# MAXIM-ADC2.net
KiCad netlist of a schematic drawn in Altium Designer
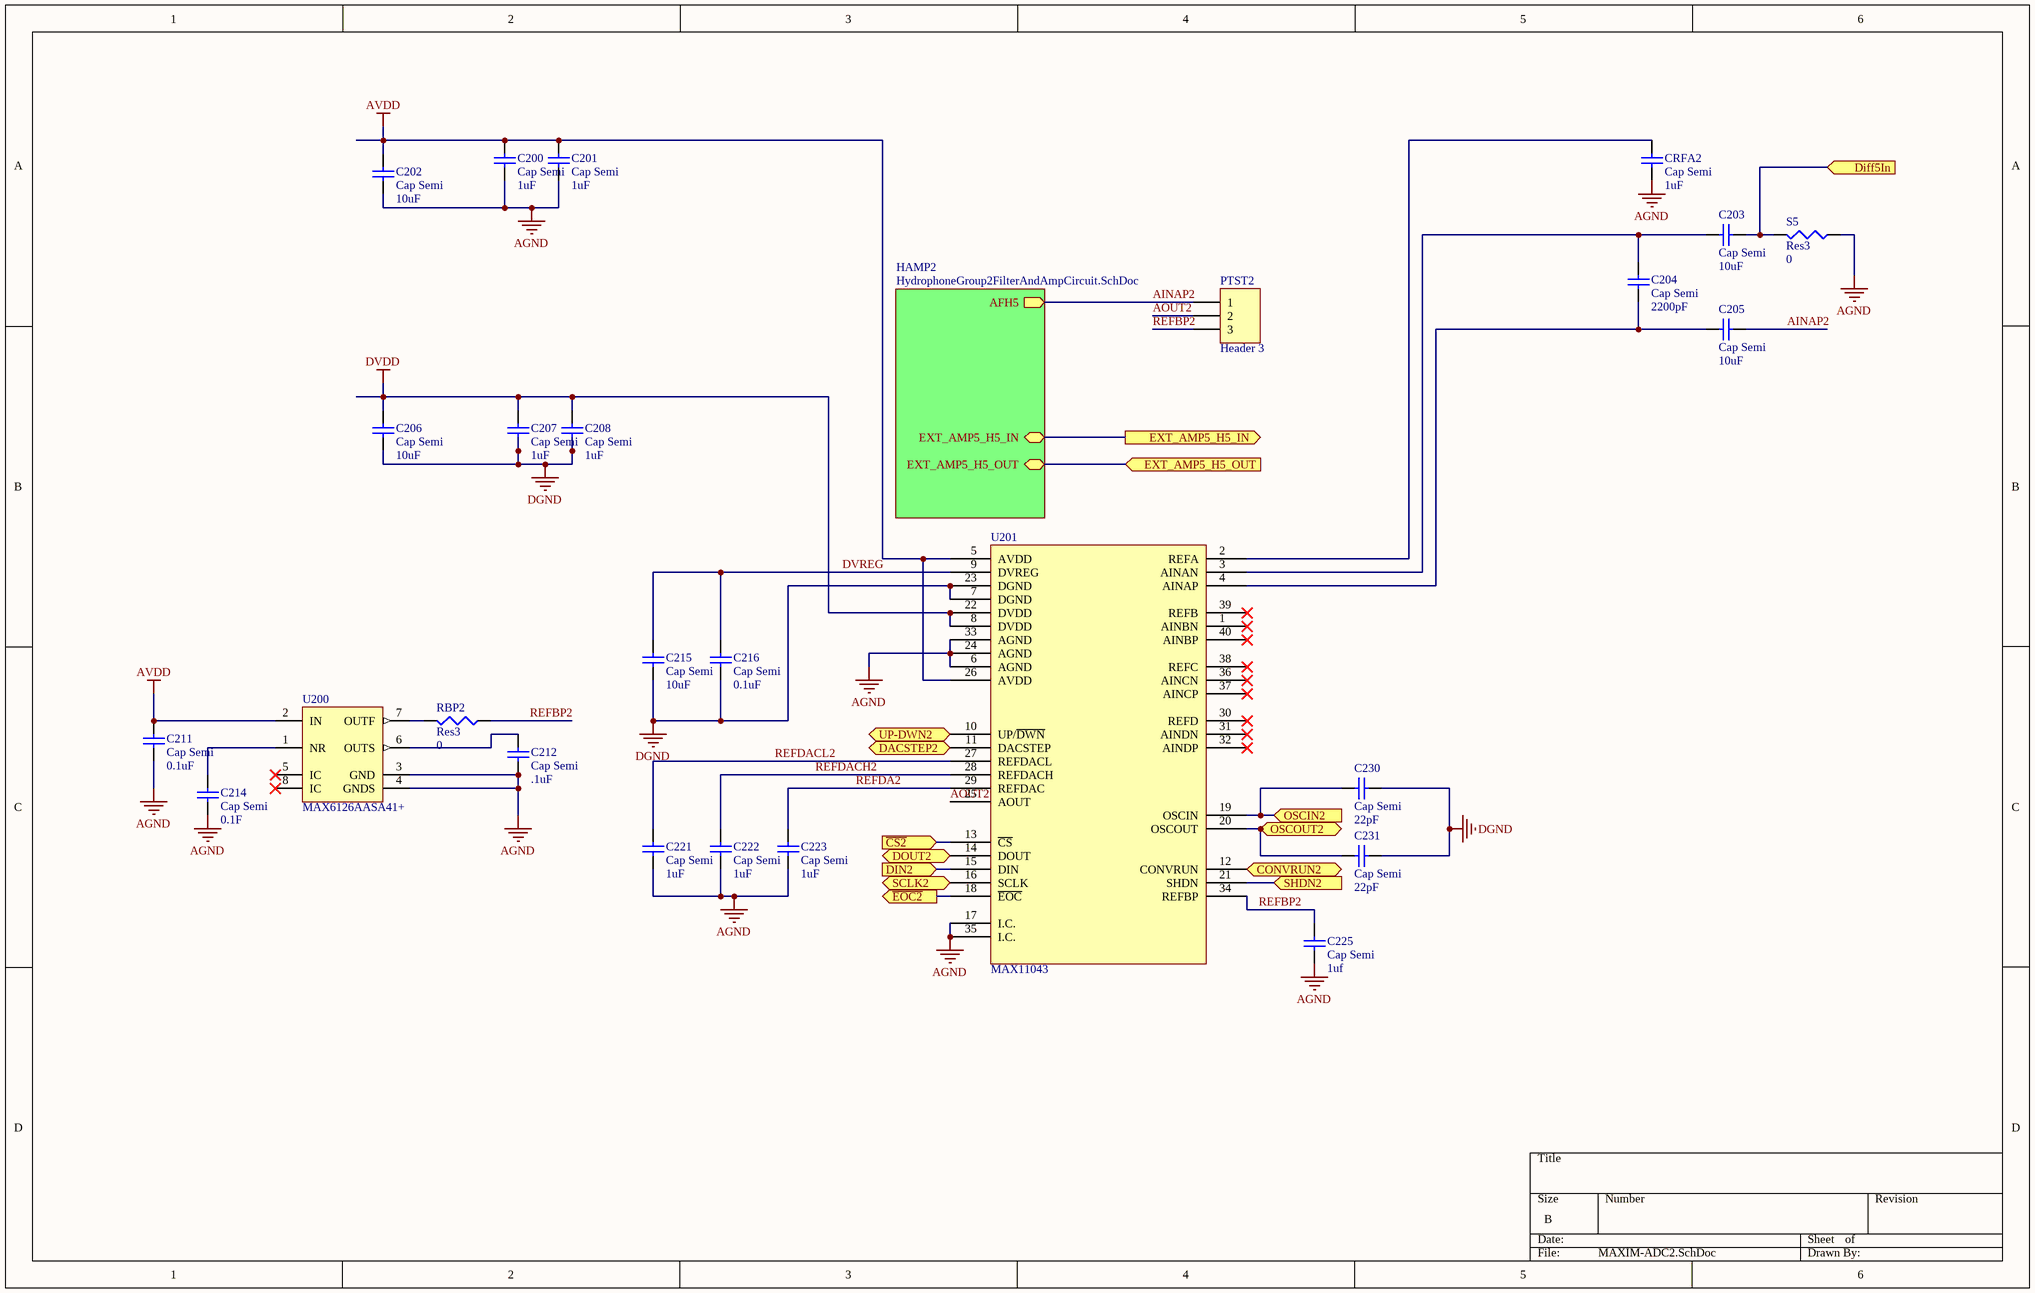
[diagram p0: MAXIM-ADC2.SchDoc]

(export (version "E")
  (design (tool "Eeschema 10.0.6"))
  (components
    (comp (ref "C200")
      (value "Cap Semi")
      (footprint "1608[0603]")
      (description "Capacitor (Semiconductor SIM Model)")
      (fields (field (name "ALTIUM_VALUE") "1uF") (field (name "PUBLISHER") "Altium Limited"))
      (libsource (lib "Miscellaneous Devices") (part "Cap Semi"))
    )
    (comp (ref "C201")
      (value "Cap Semi")
      (footprint "1608[0603]")
      (description "Capacitor (Semiconductor SIM Model)")
      (fields (field (name "ALTIUM_VALUE") "1uF") (field (name "PUBLISHER") "Altium Limited"))
      (libsource (lib "Miscellaneous Devices") (part "Cap Semi"))
    )
    (comp (ref "C202")
      (value "Cap Semi")
      (footprint "1608[0603]")
      (description "Capacitor (Semiconductor SIM Model)")
      (fields (field (name "ALTIUM_VALUE") "10uF") (field (name "PUBLISHER") "Altium Limited"))
      (libsource (lib "Miscellaneous Devices") (part "Cap Semi"))
    )
    (comp (ref "C203")
      (value "Cap Semi")
      (footprint "1608[0603]")
      (description "Capacitor (Semiconductor SIM Model)")
      (fields (field (name "ALTIUM_VALUE") "10uF") (field (name "PUBLISHER") "Altium Limited"))
      (libsource (lib "Miscellaneous Devices") (part "Cap Semi"))
    )
    (comp (ref "C204")
      (value "Cap Semi")
      (footprint "1608[0603]")
      (description "Capacitor (Semiconductor SIM Model)")
      (fields (field (name "ALTIUM_VALUE") "2200pF") (field (name "PUBLISHER") "Altium Limited"))
      (libsource (lib "Miscellaneous Devices") (part "Cap Semi"))
    )
    (comp (ref "C205")
      (value "Cap Semi")
      (footprint "1608[0603]")
      (description "Capacitor (Semiconductor SIM Model)")
      (fields (field (name "ALTIUM_VALUE") "10uF") (field (name "PUBLISHER") "Altium Limited"))
      (libsource (lib "Miscellaneous Devices") (part "Cap Semi"))
    )
    (comp (ref "C206")
      (value "Cap Semi")
      (footprint "1608[0603]")
      (description "Capacitor (Semiconductor SIM Model)")
      (fields (field (name "ALTIUM_VALUE") "10uF") (field (name "PUBLISHER") "Altium Limited"))
      (libsource (lib "Miscellaneous Devices") (part "Cap Semi"))
    )
    (comp (ref "C207")
      (value "Cap Semi")
      (footprint "1608[0603]")
      (description "Capacitor (Semiconductor SIM Model)")
      (fields (field (name "ALTIUM_VALUE") "1uF") (field (name "PUBLISHER") "Altium Limited"))
      (libsource (lib "Miscellaneous Devices") (part "Cap Semi"))
    )
    (comp (ref "C208")
      (value "Cap Semi")
      (footprint "1608[0603]")
      (description "Capacitor (Semiconductor SIM Model)")
      (fields (field (name "ALTIUM_VALUE") "1uF") (field (name "PUBLISHER") "Altium Limited"))
      (libsource (lib "Miscellaneous Devices") (part "Cap Semi"))
    )
    (comp (ref "C211")
      (value "Cap Semi")
      (footprint "1608[0603]")
      (description "Capacitor (Semiconductor SIM Model)")
      (fields (field (name "ALTIUM_VALUE") "0.1uF") (field (name "PUBLISHER") "Altium Limited"))
      (libsource (lib "Miscellaneous Devices") (part "Cap Semi"))
    )
    (comp (ref "C212")
      (value "Cap Semi")
      (footprint "1608[0603]")
      (description "Capacitor (Semiconductor SIM Model)")
      (fields (field (name "ALTIUM_VALUE") ".1uF") (field (name "PUBLISHER") "Altium Limited"))
      (libsource (lib "Miscellaneous Devices") (part "Cap Semi"))
    )
    (comp (ref "C214")
      (value "Cap Semi")
      (footprint "1608[0603]")
      (description "Capacitor (Semiconductor SIM Model)")
      (fields (field (name "ALTIUM_VALUE") "0.1F") (field (name "PUBLISHER") "Altium Limited"))
      (libsource (lib "Miscellaneous Devices") (part "Cap Semi"))
    )
    (comp (ref "C215")
      (value "Cap Semi")
      (footprint "1608[0603]")
      (description "Capacitor (Semiconductor SIM Model)")
      (fields (field (name "ALTIUM_VALUE") "10uF") (field (name "PUBLISHER") "Altium Limited"))
      (libsource (lib "Miscellaneous Devices") (part "Cap Semi"))
    )
    (comp (ref "C216")
      (value "Cap Semi")
      (footprint "1608[0603]")
      (description "Capacitor (Semiconductor SIM Model)")
      (fields (field (name "ALTIUM_VALUE") "0.1uF") (field (name "PUBLISHER") "Altium Limited"))
      (libsource (lib "Miscellaneous Devices") (part "Cap Semi"))
    )
    (comp (ref "C221")
      (value "Cap Semi")
      (footprint "1608[0603]")
      (description "Capacitor (Semiconductor SIM Model)")
      (fields (field (name "ALTIUM_VALUE") "1uF") (field (name "PUBLISHER") "Altium Limited"))
      (libsource (lib "Miscellaneous Devices") (part "Cap Semi"))
    )
    (comp (ref "C222")
      (value "Cap Semi")
      (footprint "1608[0603]")
      (description "Capacitor (Semiconductor SIM Model)")
      (fields (field (name "ALTIUM_VALUE") "1uF") (field (name "PUBLISHER") "Altium Limited"))
      (libsource (lib "Miscellaneous Devices") (part "Cap Semi"))
    )
    (comp (ref "C223")
      (value "Cap Semi")
      (footprint "1608[0603]")
      (description "Capacitor (Semiconductor SIM Model)")
      (fields (field (name "ALTIUM_VALUE") "1uF") (field (name "PUBLISHER") "Altium Limited"))
      (libsource (lib "Miscellaneous Devices") (part "Cap Semi"))
    )
    (comp (ref "C225")
      (value "Cap Semi")
      (footprint "1608[0603]")
      (description "Capacitor (Semiconductor SIM Model)")
      (fields (field (name "ALTIUM_VALUE") "1uf") (field (name "PUBLISHER") "Altium Limited"))
      (libsource (lib "Miscellaneous Devices") (part "Cap Semi"))
    )
    (comp (ref "C230")
      (value "Cap Semi")
      (footprint "1608[0603]")
      (description "Capacitor (Semiconductor SIM Model)")
      (fields (field (name "ALTIUM_VALUE") "22pF") (field (name "PUBLISHER") "Altium Limited"))
      (libsource (lib "Miscellaneous Devices") (part "Cap Semi"))
    )
    (comp (ref "C231")
      (value "Cap Semi")
      (footprint "1608[0603]")
      (description "Capacitor (Semiconductor SIM Model)")
      (fields (field (name "ALTIUM_VALUE") "22pF") (field (name "PUBLISHER") "Altium Limited"))
      (libsource (lib "Miscellaneous Devices") (part "Cap Semi"))
    )
    (comp (ref "CRFA2")
      (value "Cap Semi")
      (footprint "1608[0603]")
      (description "Capacitor (Semiconductor SIM Model)")
      (fields (field (name "ALTIUM_VALUE") "1uF") (field (name "PUBLISHER") "Altium Limited"))
      (libsource (lib "Miscellaneous Devices") (part "Cap Semi"))
    )
    (comp (ref "PTST2")
      (value "Header 3")
      (footprint "HDR1X3")
      (description "ADC2 Signal Test Header")
      (fields (field (name "PUBLISHER") "Altium Limited"))
      (libsource (lib "Miscellaneous Connectors") (part "Header 3"))
    )
    (comp (ref "RBP2")
      (value "Res3")
      (footprint "J1-0603")
      (description "Resistor")
      (fields (field (name "ALTIUM_VALUE") "0") (field (name "PUBLISHER") "Altium Limited"))
      (libsource (lib "Miscellaneous Devices") (part "Res3"))
    )
    (comp (ref "S5")
      (value "Res3")
      (footprint "J1-0603")
      (description "Resistor")
      (fields (field (name "ALTIUM_VALUE") "0") (field (name "PUBLISHER") "Altium Limited"))
      (libsource (lib "Miscellaneous Devices") (part "Res3"))
    )
    (comp (ref "U200")
      (value "MAX6126AASA41+")
      (footprint "MAXM-S8+4_M")
      (fields (field (name "MANUFACTURER") "Maxim"))
      (libsource (lib "altium-import") (part "root_0_CMP-0977-00016-1_"))
    )
    (comp (ref "U201")
      (value "MAX11043")
      (footprint "QFN50P600X600X80_HS-41N")
      (libsource (lib "Max11043") (part "MAX11043"))
    )
  )
  (nets
    (net (code "1") (name "/AINAP2") (class "Default")
      (node (ref "C205") (pin "1") (pinfunction "1_1") (pintype "passive"))
      (node (ref "PTST2") (pin "1") (pinfunction "1_1") (pintype "passive"))
    )
    (net (code "2") (name "/AOUT2") (class "Default")
      (node (ref "PTST2") (pin "2") (pinfunction "2_2") (pintype "passive"))
      (node (ref "U201") (pin "25") (pinfunction "AOUT_25") (pintype "passive"))
    )
    (net (code "3") (name "/CONVRUN2") (class "Default")
      (node (ref "U201") (pin "12") (pinfunction "CONVRUN_12") (pintype "passive"))
    )
    (net (code "4") (name "/DACSTEP2") (class "Default")
      (node (ref "U201") (pin "11") (pinfunction "DACSTEP_11") (pintype "passive"))
    )
    (net (code "5") (name "/DIN2") (class "Default")
      (node (ref "U201") (pin "15") (pinfunction "DIN_15") (pintype "passive"))
    )
    (net (code "6") (name "/DOUT2") (class "Default")
      (node (ref "U201") (pin "14") (pinfunction "DOUT_14") (pintype "passive"))
    )
    (net (code "7") (name "/DVREG") (class "Default")
      (node (ref "C215") (pin "1") (pinfunction "1_1") (pintype "passive"))
      (node (ref "C216") (pin "1") (pinfunction "1_1") (pintype "passive"))
      (node (ref "U201") (pin "9") (pinfunction "DVREG_9") (pintype "passive"))
    )
    (net (code "8") (name "/Diff5In") (class "Default")
      (node (ref "C203") (pin "1") (pinfunction "1_1") (pintype "passive"))
      (node (ref "S5") (pin "2") (pinfunction "2_2") (pintype "passive"))
    )
    (net (code "11") (name "/OSCIN2") (class "Default")
      (node (ref "C230") (pin "1") (pinfunction "1_1") (pintype "passive"))
      (node (ref "U201") (pin "19") (pinfunction "OSCIN_19") (pintype "passive"))
    )
    (net (code "12") (name "/OSCOUT2") (class "Default")
      (node (ref "C231") (pin "1") (pinfunction "1_1") (pintype "passive"))
      (node (ref "U201") (pin "20") (pinfunction "OSCOUT_20") (pintype "passive"))
    )
    (net (code "13") (name "/REFBP2") (class "Default")
      (node (ref "C225") (pin "1") (pinfunction "1_1") (pintype "passive"))
      (node (ref "PTST2") (pin "3") (pinfunction "3_3") (pintype "passive"))
      (node (ref "RBP2") (pin "1") (pinfunction "1_1") (pintype "passive"))
      (node (ref "U201") (pin "34") (pinfunction "REFBP_34") (pintype "passive"))
    )
    (net (code "14") (name "/REFDA2") (class "Default")
      (node (ref "C223") (pin "2") (pinfunction "2_2") (pintype "passive"))
      (node (ref "U201") (pin "29") (pinfunction "REFDAC_29") (pintype "passive"))
    )
    (net (code "15") (name "/REFDACH2") (class "Default")
      (node (ref "C222") (pin "1") (pinfunction "1_1") (pintype "passive"))
      (node (ref "U201") (pin "28") (pinfunction "REFDACH_28") (pintype "passive"))
    )
    (net (code "16") (name "/REFDACL2") (class "Default")
      (node (ref "C221") (pin "2") (pinfunction "2_2") (pintype "passive"))
      (node (ref "U201") (pin "27") (pinfunction "REFDACL_27") (pintype "passive"))
    )
    (net (code "17") (name "/SCLK2") (class "Default")
      (node (ref "U201") (pin "16") (pinfunction "SCLK_16") (pintype "passive"))
    )
    (net (code "18") (name "/SHDN2") (class "Default")
      (node (ref "U201") (pin "21") (pinfunction "SHDN_21") (pintype "passive"))
    )
    (net (code "19") (name "/UP-DWN2") (class "Default")
      (node (ref "U201") (pin "10") (pinfunction "UP/~{DWN}_10") (pintype "passive"))
    )
    (net (code "20") (name "/~{CS2}") (class "Default")
      (node (ref "U201") (pin "13") (pinfunction "~{CS}_13") (pintype "passive"))
    )
    (net (code "21") (name "/~{EOC2}") (class "Default")
      (node (ref "U201") (pin "18") (pinfunction "~{EOC}_18") (pintype "passive"))
    )
    (net (code "22") (name "AGND") (class "Default")
      (node (ref "C200") (pin "2") (pinfunction "2_2") (pintype "passive"))
      (node (ref "C201") (pin "2") (pinfunction "2_2") (pintype "passive"))
      (node (ref "C202") (pin "2") (pinfunction "2_2") (pintype "passive"))
      (node (ref "C211") (pin "2") (pinfunction "2_2") (pintype "passive"))
      (node (ref "C212") (pin "2") (pinfunction "2_2") (pintype "passive"))
      (node (ref "C214") (pin "2") (pinfunction "2_2") (pintype "passive"))
      (node (ref "C221") (pin "1") (pinfunction "1_1") (pintype "passive"))
      (node (ref "C222") (pin "2") (pinfunction "2_2") (pintype "passive"))
      (node (ref "C223") (pin "1") (pinfunction "1_1") (pintype "passive"))
      (node (ref "C225") (pin "2") (pinfunction "2_2") (pintype "passive"))
      (node (ref "CRFA2") (pin "1") (pinfunction "1_1") (pintype "passive"))
      (node (ref "S5") (pin "1") (pinfunction "1_1") (pintype "passive"))
      (node (ref "U200") (pin "3") (pinfunction "GND_3") (pintype "power_in"))
      (node (ref "U200") (pin "4") (pinfunction "GNDS_4") (pintype "power_in"))
      (node (ref "U201") (pin "17") (pinfunction "I.C._17") (pintype "passive"))
      (node (ref "U201") (pin "24") (pinfunction "AGND_24") (pintype "passive"))
      (node (ref "U201") (pin "33") (pinfunction "AGND_33") (pintype "passive"))
      (node (ref "U201") (pin "35") (pinfunction "I.C._35") (pintype "passive"))
      (node (ref "U201") (pin "6") (pinfunction "AGND_6") (pintype "passive"))
    )
    (net (code "23") (name "AVDD") (class "Default")
      (node (ref "C200") (pin "1") (pinfunction "1_1") (pintype "passive"))
      (node (ref "C201") (pin "1") (pinfunction "1_1") (pintype "passive"))
      (node (ref "C202") (pin "1") (pinfunction "1_1") (pintype "passive"))
      (node (ref "C211") (pin "1") (pinfunction "1_1") (pintype "passive"))
      (node (ref "U200") (pin "2") (pinfunction "IN_2") (pintype "power_in"))
      (node (ref "U201") (pin "26") (pinfunction "AVDD_26") (pintype "passive"))
      (node (ref "U201") (pin "5") (pinfunction "AVDD_5") (pintype "passive"))
    )
    (net (code "24") (name "DGND") (class "Default")
      (node (ref "C206") (pin "2") (pinfunction "2_2") (pintype "passive"))
      (node (ref "C207") (pin "2") (pinfunction "2_2") (pintype "passive"))
      (node (ref "C208") (pin "2") (pinfunction "2_2") (pintype "passive"))
      (node (ref "C215") (pin "2") (pinfunction "2_2") (pintype "passive"))
      (node (ref "C216") (pin "2") (pinfunction "2_2") (pintype "passive"))
      (node (ref "C230") (pin "2") (pinfunction "2_2") (pintype "passive"))
      (node (ref "C231") (pin "2") (pinfunction "2_2") (pintype "passive"))
      (node (ref "U201") (pin "23") (pinfunction "DGND_23") (pintype "passive"))
      (node (ref "U201") (pin "7") (pinfunction "DGND_7") (pintype "passive"))
    )
    (net (code "25") (name "DVDD") (class "Default")
      (node (ref "C206") (pin "1") (pinfunction "1_1") (pintype "passive"))
      (node (ref "C207") (pin "1") (pinfunction "1_1") (pintype "passive"))
      (node (ref "C208") (pin "1") (pinfunction "1_1") (pintype "passive"))
      (node (ref "U201") (pin "22") (pinfunction "DVDD_22") (pintype "passive"))
      (node (ref "U201") (pin "8") (pinfunction "DVDD_8") (pintype "passive"))
    )
    (net (code "26") (name "Net-(U200-NR)") (class "Default")
      (node (ref "C214") (pin "1") (pinfunction "1_1") (pintype "passive"))
      (node (ref "U200") (pin "1") (pinfunction "NR_1") (pintype "passive"))
    )
    (net (code "27") (name "Net-(U200-OUTF)") (class "Default")
      (node (ref "RBP2") (pin "2") (pinfunction "2_2") (pintype "passive"))
      (node (ref "U200") (pin "7") (pinfunction "OUTF_7") (pintype "output"))
    )
    (net (code "28") (name "Net-(U200-OUTS)") (class "Default")
      (node (ref "C212") (pin "1") (pinfunction "1_1") (pintype "passive"))
      (node (ref "U200") (pin "6") (pinfunction "OUTS_6") (pintype "output"))
    )
    (net (code "29") (name "Net-(U201-AINAN)") (class "Default")
      (node (ref "C203") (pin "2") (pinfunction "2_2") (pintype "passive"))
      (node (ref "C204") (pin "2") (pinfunction "2_2") (pintype "passive"))
      (node (ref "U201") (pin "3") (pinfunction "AINAN_3") (pintype "passive"))
    )
    (net (code "30") (name "Net-(U201-AINAP)") (class "Default")
      (node (ref "C204") (pin "1") (pinfunction "1_1") (pintype "passive"))
      (node (ref "C205") (pin "2") (pinfunction "2_2") (pintype "passive"))
      (node (ref "U201") (pin "4") (pinfunction "AINAP_4") (pintype "passive"))
    )
    (net (code "31") (name "Net-(U201-REFA)") (class "Default")
      (node (ref "CRFA2") (pin "2") (pinfunction "2_2") (pintype "passive"))
      (node (ref "U201") (pin "2") (pinfunction "REFA_2") (pintype "passive"))
    )
    (net (code "32") (name "unconnected-(U200-IC-Pad5)") (class "Default")
      (node (ref "U200") (pin "5") (pinfunction "IC_5") (pintype "passive+no_connect"))
    )
    (net (code "33") (name "unconnected-(U200-IC-Pad8)") (class "Default")
      (node (ref "U200") (pin "8") (pinfunction "IC_8") (pintype "passive+no_connect"))
    )
    (net (code "34") (name "unconnected-(U201-AINBN-Pad1)") (class "Default")
      (node (ref "U201") (pin "1") (pinfunction "AINBN_1") (pintype "passive+no_connect"))
    )
    (net (code "35") (name "unconnected-(U201-AINBP-Pad40)") (class "Default")
      (node (ref "U201") (pin "40") (pinfunction "AINBP_40") (pintype "passive+no_connect"))
    )
    (net (code "36") (name "unconnected-(U201-AINCN-Pad36)") (class "Default")
      (node (ref "U201") (pin "36") (pinfunction "AINCN_36") (pintype "passive+no_connect"))
    )
    (net (code "37") (name "unconnected-(U201-AINCP-Pad37)") (class "Default")
      (node (ref "U201") (pin "37") (pinfunction "AINCP_37") (pintype "passive+no_connect"))
    )
    (net (code "38") (name "unconnected-(U201-AINDN-Pad31)") (class "Default")
      (node (ref "U201") (pin "31") (pinfunction "AINDN_31") (pintype "passive+no_connect"))
    )
    (net (code "39") (name "unconnected-(U201-AINDP-Pad32)") (class "Default")
      (node (ref "U201") (pin "32") (pinfunction "AINDP_32") (pintype "passive+no_connect"))
    )
    (net (code "40") (name "unconnected-(U201-REFB-Pad39)") (class "Default")
      (node (ref "U201") (pin "39") (pinfunction "REFB_39") (pintype "passive+no_connect"))
    )
    (net (code "41") (name "unconnected-(U201-REFC-Pad38)") (class "Default")
      (node (ref "U201") (pin "38") (pinfunction "REFC_38") (pintype "passive+no_connect"))
    )
    (net (code "42") (name "unconnected-(U201-REFD-Pad30)") (class "Default")
      (node (ref "U201") (pin "30") (pinfunction "REFD_30") (pintype "passive+no_connect"))
    )
  )
)
